# saunamadis.net
KiCad netlist of a schematic drawn in Altium Designer
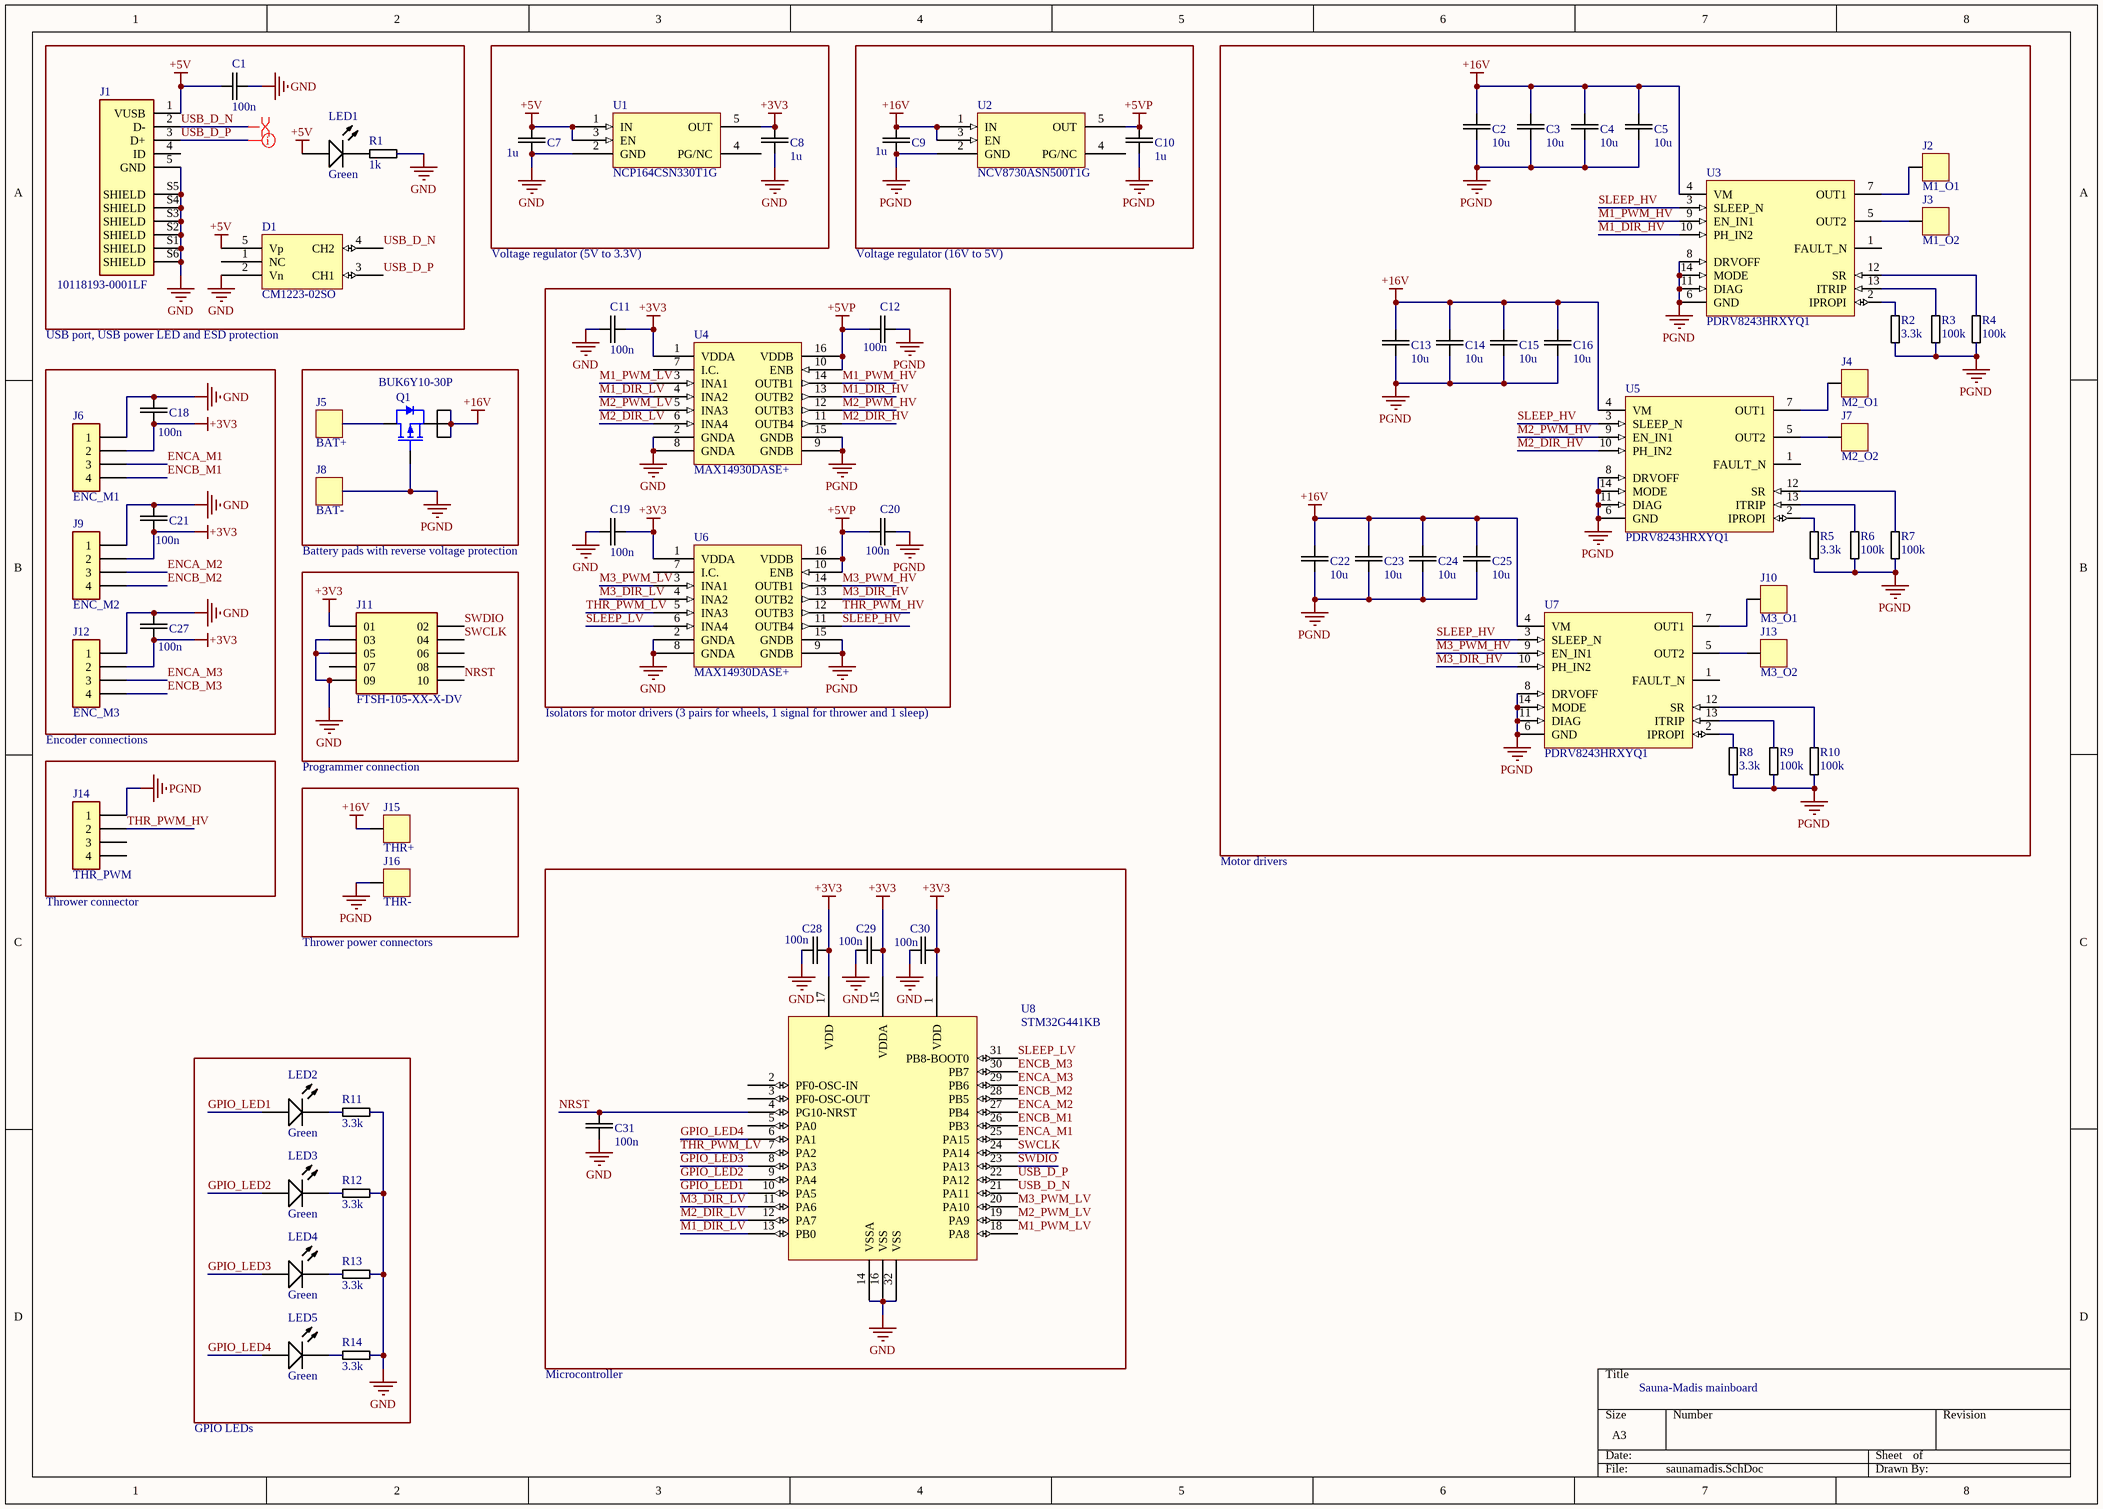
[diagram p0: saunamadis.SchDoc]

(export (version "E")
  (design (tool "Eeschema 10.0.6"))
  (components
    (comp (ref "C1")
      (value "0603C")
      (footprint "0603R")
      (description "Capacitor")
      (fields (field (name "C") "100n"))
      (libsource (lib "comp") (part "0603C"))
    )
    (comp (ref "C2")
      (value "0603C")
      (footprint "1206 cap")
      (description "Capacitor")
      (fields (field (name "C") "10u"))
      (libsource (lib "comp") (part "0603C"))
    )
    (comp (ref "C3")
      (value "0603C")
      (footprint "1206 cap")
      (description "Capacitor")
      (fields (field (name "C") "10u"))
      (libsource (lib "comp") (part "0603C"))
    )
    (comp (ref "C4")
      (value "0603C")
      (footprint "1206 cap")
      (description "Capacitor")
      (fields (field (name "C") "10u"))
      (libsource (lib "comp") (part "0603C"))
    )
    (comp (ref "C5")
      (value "0603C")
      (footprint "1206 cap")
      (description "Capacitor")
      (fields (field (name "C") "10u"))
      (libsource (lib "comp") (part "0603C"))
    )
    (comp (ref "C7")
      (value "0603C")
      (footprint "0603R")
      (description "Capacitor")
      (fields (field (name "C") "1u"))
      (libsource (lib "comp") (part "0603C"))
    )
    (comp (ref "C8")
      (value "0603C")
      (footprint "0603R")
      (description "Capacitor")
      (fields (field (name "C") "1u"))
      (libsource (lib "comp") (part "0603C"))
    )
    (comp (ref "C9")
      (value "0603C")
      (footprint "0603R")
      (description "Capacitor")
      (fields (field (name "C") "1u"))
      (libsource (lib "comp") (part "0603C"))
    )
    (comp (ref "C10")
      (value "0603C")
      (footprint "0603R")
      (description "Capacitor")
      (fields (field (name "C") "1u"))
      (libsource (lib "comp") (part "0603C"))
    )
    (comp (ref "C11")
      (value "0603C")
      (footprint "0603R")
      (description "Capacitor")
      (fields (field (name "C") "100n"))
      (libsource (lib "comp") (part "0603C"))
    )
    (comp (ref "C12")
      (value "0603C")
      (footprint "0603R")
      (description "Capacitor")
      (fields (field (name "C") "100n"))
      (libsource (lib "comp") (part "0603C"))
    )
    (comp (ref "C13")
      (value "0603C")
      (footprint "1206 cap")
      (description "Capacitor")
      (fields (field (name "C") "10u"))
      (libsource (lib "comp") (part "0603C"))
    )
    (comp (ref "C14")
      (value "0603C")
      (footprint "1206 cap")
      (description "Capacitor")
      (fields (field (name "C") "10u"))
      (libsource (lib "comp") (part "0603C"))
    )
    (comp (ref "C15")
      (value "0603C")
      (footprint "1206 cap")
      (description "Capacitor")
      (fields (field (name "C") "10u"))
      (libsource (lib "comp") (part "0603C"))
    )
    (comp (ref "C16")
      (value "0603C")
      (footprint "1206 cap")
      (description "Capacitor")
      (fields (field (name "C") "10u"))
      (libsource (lib "comp") (part "0603C"))
    )
    (comp (ref "C18")
      (value "0603C")
      (footprint "0603R")
      (description "Capacitor")
      (fields (field (name "C") "100n"))
      (libsource (lib "comp") (part "0603C"))
    )
    (comp (ref "C19")
      (value "0603C")
      (footprint "0603R")
      (description "Capacitor")
      (fields (field (name "C") "100n"))
      (libsource (lib "comp") (part "0603C"))
    )
    (comp (ref "C20")
      (value "0603C")
      (footprint "0603R")
      (description "Capacitor")
      (fields (field (name "C") "100n"))
      (libsource (lib "comp") (part "0603C"))
    )
    (comp (ref "C21")
      (value "0603C")
      (footprint "0603R")
      (description "Capacitor")
      (fields (field (name "C") "100n"))
      (libsource (lib "comp") (part "0603C"))
    )
    (comp (ref "C22")
      (value "0603C")
      (footprint "1206 cap")
      (description "Capacitor")
      (fields (field (name "C") "10u"))
      (libsource (lib "comp") (part "0603C"))
    )
    (comp (ref "C23")
      (value "0603C")
      (footprint "1206 cap")
      (description "Capacitor")
      (fields (field (name "C") "10u"))
      (libsource (lib "comp") (part "0603C"))
    )
    (comp (ref "C24")
      (value "0603C")
      (footprint "1206 cap")
      (description "Capacitor")
      (fields (field (name "C") "10u"))
      (libsource (lib "comp") (part "0603C"))
    )
    (comp (ref "C25")
      (value "0603C")
      (footprint "1206 cap")
      (description "Capacitor")
      (fields (field (name "C") "10u"))
      (libsource (lib "comp") (part "0603C"))
    )
    (comp (ref "C27")
      (value "0603C")
      (footprint "0603R")
      (description "Capacitor")
      (fields (field (name "C") "100n"))
      (libsource (lib "comp") (part "0603C"))
    )
    (comp (ref "C28")
      (value "0603C")
      (footprint "0603R")
      (description "Capacitor")
      (fields (field (name "C") "100n"))
      (libsource (lib "comp") (part "0603C"))
    )
    (comp (ref "C29")
      (value "0603C")
      (footprint "0603R")
      (description "Capacitor")
      (fields (field (name "C") "100n"))
      (libsource (lib "comp") (part "0603C"))
    )
    (comp (ref "C30")
      (value "0603C")
      (footprint "0603R")
      (description "Capacitor")
      (fields (field (name "C") "100n"))
      (libsource (lib "comp") (part "0603C"))
    )
    (comp (ref "C31")
      (value "0603C")
      (footprint "0603R")
      (description "Capacitor")
      (fields (field (name "C") "100n"))
      (libsource (lib "comp") (part "0603C"))
    )
    (comp (ref "D1")
      (value "CM1223-02SO")
      (footprint "CM1223-02SO")
      (description "TVS diode")
      (libsource (lib "comp") (part "CM1223-02SO"))
    )
    (comp (ref "J1")
      (value "10118193-0001LF")
      (footprint "FCI_10118193-0001LF")
      (description "USB - micro B USB 2.0 Receptacle Connector 5 Position Surface Mount, Right Angle; Through Hole")
      (fields (field (name "MF") "Amphenol ICC"))
      (libsource (lib "comp") (part "10118193-0001LF"))
    )
    (comp (ref "J2")
      (value "Pad")
      (footprint "Pad")
      (description "PAD")
      (fields (field (name "NAME") "M1_O1"))
      (libsource (lib "comp") (part "Pad"))
    )
    (comp (ref "J3")
      (value "Pad")
      (footprint "Pad")
      (description "PAD")
      (fields (field (name "NAME") "M1_O2"))
      (libsource (lib "comp") (part "Pad"))
    )
    (comp (ref "J4")
      (value "Pad")
      (footprint "Pad")
      (description "PAD")
      (fields (field (name "NAME") "M2_O1"))
      (libsource (lib "comp") (part "Pad"))
    )
    (comp (ref "J5")
      (value "Pad")
      (footprint "Pad")
      (description "PAD")
      (fields (field (name "NAME") "BAT+"))
      (libsource (lib "") (part "Pad_1"))
    )
    (comp (ref "J6")
      (value "ENC_M1")
      (footprint "TE_7-215079-4")
      (description "Micro-MaTch 4 Position 1.27 mm Pitch Vertical Female-on-Board Connector")
      (fields (field (name "MP") "7-215079-4") (field (name "MF") "TE Connectivity"))
      (libsource (lib "comp") (part "7-215079-4"))
    )
    (comp (ref "J7")
      (value "Pad")
      (footprint "Pad")
      (description "PAD")
      (fields (field (name "NAME") "M2_O2"))
      (libsource (lib "comp") (part "Pad"))
    )
    (comp (ref "J8")
      (value "Pad")
      (footprint "Pad")
      (description "PAD")
      (fields (field (name "NAME") "BAT-"))
      (libsource (lib "") (part "Pad_1"))
    )
    (comp (ref "J9")
      (value "ENC_M2")
      (footprint "TE_7-215079-4")
      (description "Micro-MaTch 4 Position 1.27 mm Pitch Vertical Female-on-Board Connector")
      (fields (field (name "MP") "7-215079-4") (field (name "MF") "TE Connectivity"))
      (libsource (lib "comp") (part "7-215079-4"))
    )
    (comp (ref "J10")
      (value "Pad")
      (footprint "Pad")
      (description "PAD")
      (fields (field (name "NAME") "M3_O1"))
      (libsource (lib "comp") (part "Pad"))
    )
    (comp (ref "J11")
      (value "FTSH-105-XX-X-DV")
      (footprint "SAMTEC_FTSH-105-XX-X-DV")
      (description "Connector Header Surface Mount 10 position 0.050\" (1.27mm)")
      (libsource (lib "comp") (part "FTSH-105-XX-X-DV"))
    )
    (comp (ref "J12")
      (value "ENC_M3")
      (footprint "TE_7-215079-4")
      (description "Micro-MaTch 4 Position 1.27 mm Pitch Vertical Female-on-Board Connector")
      (fields (field (name "MP") "7-215079-4") (field (name "MF") "TE Connectivity"))
      (libsource (lib "comp") (part "7-215079-4"))
    )
    (comp (ref "J13")
      (value "Pad")
      (footprint "Pad")
      (description "PAD")
      (fields (field (name "NAME") "M3_O2"))
      (libsource (lib "comp") (part "Pad"))
    )
    (comp (ref "J14")
      (value "THR_PWM")
      (footprint "TE_7-215079-4")
      (description "Micro-MaTch 4 Position 1.27 mm Pitch Vertical Female-on-Board Connector")
      (fields (field (name "MP") "7-215079-4") (field (name "MF") "TE Connectivity"))
      (libsource (lib "comp") (part "7-215079-4"))
    )
    (comp (ref "J15")
      (value "Pad")
      (footprint "Pad")
      (description "PAD")
      (fields (field (name "NAME") "THR+"))
      (libsource (lib "comp") (part "Pad"))
    )
    (comp (ref "J16")
      (value "Pad")
      (footprint "Pad")
      (description "PAD")
      (fields (field (name "NAME") "THR-"))
      (libsource (lib "comp") (part "Pad"))
    )
    (comp (ref "LED1")
      (value "LED")
      (footprint "LEDwhite0603")
      (description "led")
      (fields (field (name "COLOR") "Green"))
      (libsource (lib "comp") (part "LED"))
    )
    (comp (ref "LED2")
      (value "LED")
      (footprint "LEDwhite0603")
      (description "led")
      (fields (field (name "COLOR") "Green"))
      (libsource (lib "comp") (part "LED"))
    )
    (comp (ref "LED3")
      (value "LED")
      (footprint "LEDwhite0603")
      (description "led")
      (fields (field (name "COLOR") "Green"))
      (libsource (lib "comp") (part "LED"))
    )
    (comp (ref "LED4")
      (value "LED")
      (footprint "LEDwhite0603")
      (description "led")
      (fields (field (name "COLOR") "Green"))
      (libsource (lib "comp") (part "LED"))
    )
    (comp (ref "LED5")
      (value "LED")
      (footprint "LEDwhite0603")
      (description "led")
      (fields (field (name "COLOR") "Green"))
      (libsource (lib "comp") (part "LED"))
    )
    (comp (ref "Q1")
      (value "BUK6Y10-30P")
      (footprint "BUK6Y10-30P")
      (description "Reverse voltage protection")
      (libsource (lib "comp") (part "BUK6Y10-30P"))
    )
    (comp (ref "R1")
      (value "0603R")
      (footprint "0603R")
      (description "resistor")
      (fields (field (name "RESISTANCE") "1k"))
      (libsource (lib "comp") (part "0603R"))
    )
    (comp (ref "R2")
      (value "0603R")
      (footprint "0603R")
      (description "resistor")
      (fields (field (name "RESISTANCE") "3.3k"))
      (libsource (lib "comp") (part "0603R"))
    )
    (comp (ref "R3")
      (value "0603R")
      (footprint "0603R")
      (description "resistor")
      (fields (field (name "RESISTANCE") "100k"))
      (libsource (lib "comp") (part "0603R"))
    )
    (comp (ref "R4")
      (value "0603R")
      (footprint "0603R")
      (description "resistor")
      (fields (field (name "RESISTANCE") "100k"))
      (libsource (lib "comp") (part "0603R"))
    )
    (comp (ref "R5")
      (value "0603R")
      (footprint "0603R")
      (description "resistor")
      (fields (field (name "RESISTANCE") "3.3k"))
      (libsource (lib "comp") (part "0603R"))
    )
    (comp (ref "R6")
      (value "0603R")
      (footprint "0603R")
      (description "resistor")
      (fields (field (name "RESISTANCE") "100k"))
      (libsource (lib "comp") (part "0603R"))
    )
    (comp (ref "R7")
      (value "0603R")
      (footprint "0603R")
      (description "resistor")
      (fields (field (name "RESISTANCE") "100k"))
      (libsource (lib "comp") (part "0603R"))
    )
    (comp (ref "R8")
      (value "0603R")
      (footprint "0603R")
      (description "resistor")
      (fields (field (name "RESISTANCE") "3.3k"))
      (libsource (lib "comp") (part "0603R"))
    )
    (comp (ref "R9")
      (value "0603R")
      (footprint "0603R")
      (description "resistor")
      (fields (field (name "RESISTANCE") "100k"))
      (libsource (lib "comp") (part "0603R"))
    )
    (comp (ref "R10")
      (value "0603R")
      (footprint "0603R")
      (description "resistor")
      (fields (field (name "RESISTANCE") "100k"))
      (libsource (lib "comp") (part "0603R"))
    )
    (comp (ref "R11")
      (value "0603R")
      (footprint "0603R")
      (description "resistor")
      (fields (field (name "RESISTANCE") "3.3k"))
      (libsource (lib "comp") (part "0603R"))
    )
    (comp (ref "R12")
      (value "0603R")
      (footprint "0603R")
      (description "resistor")
      (fields (field (name "RESISTANCE") "3.3k"))
      (libsource (lib "comp") (part "0603R"))
    )
    (comp (ref "R13")
      (value "0603R")
      (footprint "0603R")
      (description "resistor")
      (fields (field (name "RESISTANCE") "3.3k"))
      (libsource (lib "comp") (part "0603R"))
    )
    (comp (ref "R14")
      (value "0603R")
      (footprint "0603R")
      (description "resistor")
      (fields (field (name "RESISTANCE") "3.3k"))
      (libsource (lib "comp") (part "0603R"))
    )
    (comp (ref "U1")
      (value "NCP164CSN330T1G")
      (footprint "NCP164CSN330T1G/NCV8730ASN500T1G")
      (description "Voltage regulator for microcontroller")
      (libsource (lib "comp") (part "NCP164CSN330T1G"))
    )
    (comp (ref "U2")
      (value "NCV8730ASN500T1G")
      (footprint "NCP164CSN330T1G/NCV8730ASN500T1G")
      (description "Voltage regulator at the motor driver’s side")
      (libsource (lib "comp") (part "NCV8730ASN500T1G"))
    )
    (comp (ref "U3")
      (value "PDRV8243HRXYQ1")
      (footprint "PDRV8243HRXYQ1")
      (description "Motor driver")
      (libsource (lib "comp") (part "PDRV8243HRXYQ1"))
    )
    (comp (ref "U4")
      (value "MAX14930DASE+")
      (footprint "MAX14930DASE+")
      (description "isolator")
      (libsource (lib "comp") (part "MAX14930DASE+"))
    )
    (comp (ref "U5")
      (value "PDRV8243HRXYQ1")
      (footprint "PDRV8243HRXYQ1")
      (description "Motor driver")
      (libsource (lib "comp") (part "PDRV8243HRXYQ1"))
    )
    (comp (ref "U6")
      (value "MAX14930DASE+")
      (footprint "MAX14930DASE+")
      (description "isolator")
      (libsource (lib "comp") (part "MAX14930DASE+"))
    )
    (comp (ref "U7")
      (value "PDRV8243HRXYQ1")
      (footprint "PDRV8243HRXYQ1")
      (description "Motor driver")
      (libsource (lib "comp") (part "PDRV8243HRXYQ1"))
    )
    (comp (ref "U8")
      (value "STM32G441KB")
      (footprint "TQFP80P900X900X160-32N")
      (description "microcontroller")
      (libsource (lib "comp") (part "STM32G441KB"))
    )
  )
  (nets
    (net (code "1") (name "+3V3") (class "Default")
      (node (ref "C11") (pin "1") (pinfunction "1_1") (pintype "passive"))
      (node (ref "C18") (pin "1") (pinfunction "1_1") (pintype "passive"))
      (node (ref "C19") (pin "1") (pinfunction "1_1") (pintype "passive"))
      (node (ref "C21") (pin "1") (pinfunction "1_1") (pintype "passive"))
      (node (ref "C27") (pin "1") (pinfunction "1_1") (pintype "passive"))
      (node (ref "C28") (pin "1") (pinfunction "1_1") (pintype "passive"))
      (node (ref "C29") (pin "1") (pinfunction "1_1") (pintype "passive"))
      (node (ref "C30") (pin "1") (pinfunction "1_1") (pintype "passive"))
      (node (ref "C8") (pin "2") (pinfunction "2_2") (pintype "passive"))
      (node (ref "J11") (pin "01") (pinfunction "01_01") (pintype "passive"))
      (node (ref "J12") (pin "2") (pinfunction "2_2") (pintype "passive"))
      (node (ref "J6") (pin "2") (pinfunction "2_2") (pintype "passive"))
      (node (ref "J9") (pin "2") (pinfunction "2_2") (pintype "passive"))
      (node (ref "U1") (pin "5") (pinfunction "OUT_5") (pintype "power_in"))
      (node (ref "U4") (pin "1") (pinfunction "VDDA_1") (pintype "power_in"))
      (node (ref "U6") (pin "1") (pinfunction "VDDA_1") (pintype "power_in"))
      (node (ref "U8") (pin "1") (pinfunction "VDD_1") (pintype "power_in"))
      (node (ref "U8") (pin "15") (pinfunction "VDDA_15") (pintype "power_in"))
      (node (ref "U8") (pin "17") (pinfunction "VDD_17") (pintype "power_in"))
    )
    (net (code "2") (name "+5V") (class "Default")
      (node (ref "C1") (pin "1") (pinfunction "1_1") (pintype "passive"))
      (node (ref "C7") (pin "2") (pinfunction "2_2") (pintype "passive"))
      (node (ref "D1") (pin "5") (pinfunction "Vp_5") (pintype "power_in"))
      (node (ref "J1") (pin "1") (pinfunction "VUSB_1") (pintype "passive"))
      (node (ref "LED1") (pin "1") (pinfunction "A_1") (pintype "passive"))
      (node (ref "U1") (pin "1") (pinfunction "IN_1") (pintype "input"))
      (node (ref "U1") (pin "3") (pinfunction "EN_3") (pintype "input"))
    )
    (net (code "3") (name "+5VP") (class "Default")
      (node (ref "C10") (pin "2") (pinfunction "2_2") (pintype "passive"))
      (node (ref "C12") (pin "2") (pinfunction "2_2") (pintype "passive"))
      (node (ref "C20") (pin "2") (pinfunction "2_2") (pintype "passive"))
      (node (ref "U2") (pin "5") (pinfunction "OUT_5") (pintype "power_in"))
      (node (ref "U4") (pin "10") (pinfunction "ENB_10") (pintype "input"))
      (node (ref "U4") (pin "16") (pinfunction "VDDB_16") (pintype "power_in"))
      (node (ref "U6") (pin "10") (pinfunction "ENB_10") (pintype "input"))
      (node (ref "U6") (pin "16") (pinfunction "VDDB_16") (pintype "power_in"))
    )
    (net (code "4") (name "+16V") (class "Default")
      (node (ref "C13") (pin "1") (pinfunction "1_1") (pintype "passive"))
      (node (ref "C14") (pin "1") (pinfunction "1_1") (pintype "passive"))
      (node (ref "C15") (pin "1") (pinfunction "1_1") (pintype "passive"))
      (node (ref "C16") (pin "1") (pinfunction "1_1") (pintype "passive"))
      (node (ref "C2") (pin "1") (pinfunction "1_1") (pintype "passive"))
      (node (ref "C22") (pin "1") (pinfunction "1_1") (pintype "passive"))
      (node (ref "C23") (pin "1") (pinfunction "1_1") (pintype "passive"))
      (node (ref "C24") (pin "1") (pinfunction "1_1") (pintype "passive"))
      (node (ref "C25") (pin "1") (pinfunction "1_1") (pintype "passive"))
      (node (ref "C3") (pin "1") (pinfunction "1_1") (pintype "passive"))
      (node (ref "C4") (pin "1") (pinfunction "1_1") (pintype "passive"))
      (node (ref "C5") (pin "1") (pinfunction "1_1") (pintype "passive"))
      (node (ref "C9") (pin "2") (pinfunction "2_2") (pintype "passive"))
      (node (ref "J15") (pin "1") (pinfunction "1_1") (pintype "passive"))
      (node (ref "Q1") (pin "1") (pinfunction "SOURCE_1") (pintype "passive"))
      (node (ref "Q1") (pin "2") (pinfunction "SOURCE_2") (pintype "passive"))
      (node (ref "Q1") (pin "3") (pinfunction "SOURCE_3") (pintype "passive"))
      (node (ref "U2") (pin "1") (pinfunction "IN_1") (pintype "input"))
      (node (ref "U2") (pin "3") (pinfunction "EN_3") (pintype "input"))
      (node (ref "U3") (pin "4") (pinfunction "VM_4") (pintype "power_in"))
      (node (ref "U5") (pin "4") (pinfunction "VM_4") (pintype "power_in"))
      (node (ref "U7") (pin "4") (pinfunction "VM_4") (pintype "power_in"))
    )
    (net (code "5") (name "/ENCA_M1") (class "Default")
      (node (ref "J6") (pin "3") (pinfunction "3_3") (pintype "passive"))
      (node (ref "U8") (pin "25") (pinfunction "PA15_25") (pintype "bidirectional"))
    )
    (net (code "6") (name "/ENCA_M2") (class "Default")
      (node (ref "J9") (pin "3") (pinfunction "3_3") (pintype "passive"))
      (node (ref "U8") (pin "27") (pinfunction "PB4_27") (pintype "bidirectional"))
    )
    (net (code "7") (name "/ENCA_M3") (class "Default")
      (node (ref "J12") (pin "3") (pinfunction "3_3") (pintype "passive"))
      (node (ref "U8") (pin "29") (pinfunction "PB6_29") (pintype "bidirectional"))
    )
    (net (code "8") (name "/ENCB_M1") (class "Default")
      (node (ref "J6") (pin "4") (pinfunction "4_4") (pintype "passive"))
      (node (ref "U8") (pin "26") (pinfunction "PB3_26") (pintype "bidirectional"))
    )
    (net (code "9") (name "/ENCB_M2") (class "Default")
      (node (ref "J9") (pin "4") (pinfunction "4_4") (pintype "passive"))
      (node (ref "U8") (pin "28") (pinfunction "PB5_28") (pintype "bidirectional"))
    )
    (net (code "10") (name "/ENCB_M3") (class "Default")
      (node (ref "J12") (pin "4") (pinfunction "4_4") (pintype "passive"))
      (node (ref "U8") (pin "30") (pinfunction "PB7_30") (pintype "bidirectional"))
    )
    (net (code "11") (name "/GPIO_LED1") (class "Default")
      (node (ref "LED2") (pin "1") (pinfunction "A_1") (pintype "passive"))
      (node (ref "U8") (pin "10") (pinfunction "PA5_10") (pintype "bidirectional"))
    )
    (net (code "12") (name "/GPIO_LED2") (class "Default")
      (node (ref "LED3") (pin "1") (pinfunction "A_1") (pintype "passive"))
      (node (ref "U8") (pin "9") (pinfunction "PA4_9") (pintype "bidirectional"))
    )
    (net (code "13") (name "/GPIO_LED3") (class "Default")
      (node (ref "LED4") (pin "1") (pinfunction "A_1") (pintype "passive"))
      (node (ref "U8") (pin "8") (pinfunction "PA3_8") (pintype "bidirectional"))
    )
    (net (code "14") (name "/GPIO_LED4") (class "Default")
      (node (ref "LED5") (pin "1") (pinfunction "A_1") (pintype "passive"))
      (node (ref "U8") (pin "6") (pinfunction "PA1_6") (pintype "bidirectional"))
    )
    (net (code "15") (name "/M1_DIR_HV") (class "Default")
      (node (ref "U3") (pin "10") (pinfunction "PH_IN2_10") (pintype "input"))
      (node (ref "U4") (pin "13") (pinfunction "OUTB2_13") (pintype "output"))
    )
    (net (code "16") (name "/M1_DIR_LV") (class "Default")
      (node (ref "U4") (pin "4") (pinfunction "INA2_4") (pintype "input"))
      (node (ref "U8") (pin "13") (pinfunction "PB0_13") (pintype "bidirectional"))
    )
    (net (code "17") (name "/M1_PWM_HV") (class "Default")
      (node (ref "U3") (pin "9") (pinfunction "EN_IN1_9") (pintype "input"))
      (node (ref "U4") (pin "14") (pinfunction "OUTB1_14") (pintype "output"))
    )
    (net (code "18") (name "/M1_PWM_LV") (class "Default")
      (node (ref "U4") (pin "3") (pinfunction "INA1_3") (pintype "input"))
      (node (ref "U8") (pin "18") (pinfunction "PA8_18") (pintype "bidirectional"))
    )
    (net (code "19") (name "/M2_DIR_HV") (class "Default")
      (node (ref "U4") (pin "11") (pinfunction "OUTB4_11") (pintype "output"))
      (node (ref "U5") (pin "10") (pinfunction "PH_IN2_10") (pintype "input"))
    )
    (net (code "20") (name "/M2_DIR_LV") (class "Default")
      (node (ref "U4") (pin "6") (pinfunction "INA4_6") (pintype "input"))
      (node (ref "U8") (pin "12") (pinfunction "PA7_12") (pintype "bidirectional"))
    )
    (net (code "21") (name "/M2_PWM_HV") (class "Default")
      (node (ref "U4") (pin "12") (pinfunction "OUTB3_12") (pintype "output"))
      (node (ref "U5") (pin "9") (pinfunction "EN_IN1_9") (pintype "input"))
    )
    (net (code "22") (name "/M2_PWM_LV") (class "Default")
      (node (ref "U4") (pin "5") (pinfunction "INA3_5") (pintype "input"))
      (node (ref "U8") (pin "19") (pinfunction "PA9_19") (pintype "bidirectional"))
    )
    (net (code "23") (name "/M3_DIR_HV") (class "Default")
      (node (ref "U6") (pin "13") (pinfunction "OUTB2_13") (pintype "output"))
      (node (ref "U7") (pin "10") (pinfunction "PH_IN2_10") (pintype "input"))
    )
    (net (code "24") (name "/M3_DIR_LV") (class "Default")
      (node (ref "U6") (pin "4") (pinfunction "INA2_4") (pintype "input"))
      (node (ref "U8") (pin "11") (pinfunction "PA6_11") (pintype "bidirectional"))
    )
    (net (code "25") (name "/M3_PWM_HV") (class "Default")
      (node (ref "U6") (pin "14") (pinfunction "OUTB1_14") (pintype "output"))
      (node (ref "U7") (pin "9") (pinfunction "EN_IN1_9") (pintype "input"))
    )
    (net (code "26") (name "/M3_PWM_LV") (class "Default")
      (node (ref "U6") (pin "3") (pinfunction "INA1_3") (pintype "input"))
      (node (ref "U8") (pin "20") (pinfunction "PA10_20") (pintype "bidirectional"))
    )
    (net (code "27") (name "/NRST") (class "Default")
      (node (ref "C31") (pin "1") (pinfunction "1_1") (pintype "passive"))
      (node (ref "J11") (pin "10") (pinfunction "10_10") (pintype "passive"))
      (node (ref "U8") (pin "4") (pinfunction "PG10-NRST_4") (pintype "bidirectional"))
    )
    (net (code "28") (name "/SLEEP_HV") (class "Default")
      (node (ref "U3") (pin "3") (pinfunction "SLEEP_N_3") (pintype "input"))
      (node (ref "U5") (pin "3") (pinfunction "SLEEP_N_3") (pintype "input"))
      (node (ref "U6") (pin "11") (pinfunction "OUTB4_11") (pintype "output"))
      (node (ref "U7") (pin "3") (pinfunction "SLEEP_N_3") (pintype "input"))
    )
    (net (code "29") (name "/SLEEP_LV") (class "Default")
      (node (ref "U6") (pin "6") (pinfunction "INA4_6") (pintype "input"))
      (node (ref "U8") (pin "31") (pinfunction "PB8-BOOT0_31") (pintype "bidirectional"))
    )
    (net (code "30") (name "/SWCLK") (class "Default")
      (node (ref "J11") (pin "04") (pinfunction "04_04") (pintype "passive"))
      (node (ref "U8") (pin "24") (pinfunction "PA14_24") (pintype "bidirectional"))
    )
    (net (code "31") (name "/SWDIO") (class "Default")
      (node (ref "J11") (pin "02") (pinfunction "02_02") (pintype "passive"))
      (node (ref "U8") (pin "23") (pinfunction "PA13_23") (pintype "bidirectional"))
    )
    (net (code "32") (name "/THR_PWM_HV") (class "Default")
      (node (ref "J14") (pin "2") (pinfunction "2_2") (pintype "passive"))
      (node (ref "U6") (pin "12") (pinfunction "OUTB3_12") (pintype "output"))
    )
    (net (code "33") (name "/THR_PWM_LV") (class "Default")
      (node (ref "U6") (pin "5") (pinfunction "INA3_5") (pintype "input"))
      (node (ref "U8") (pin "7") (pinfunction "PA2_7") (pintype "bidirectional"))
    )
    (net (code "34") (name "/USB_D_N") (class "Default")
      (node (ref "D1") (pin "4") (pinfunction "CH2_4") (pintype "bidirectional"))
      (node (ref "J1") (pin "2") (pinfunction "D-_2") (pintype "passive"))
      (node (ref "U8") (pin "21") (pinfunction "PA11_21") (pintype "bidirectional"))
    )
    (net (code "35") (name "/USB_D_P") (class "Default")
      (node (ref "D1") (pin "3") (pinfunction "CH1_3") (pintype "bidirectional"))
      (node (ref "J1") (pin "3") (pinfunction "D+_3") (pintype "passive"))
      (node (ref "U8") (pin "22") (pinfunction "PA12_22") (pintype "bidirectional"))
    )
    (net (code "36") (name "GND") (class "Default")
      (node (ref "C1") (pin "2") (pinfunction "2_2") (pintype "passive"))
      (node (ref "C11") (pin "2") (pinfunction "2_2") (pintype "passive"))
      (node (ref "C18") (pin "2") (pinfunction "2_2") (pintype "passive"))
      (node (ref "C19") (pin "2") (pinfunction "2_2") (pintype "passive"))
      (node (ref "C21") (pin "2") (pinfunction "2_2") (pintype "passive"))
      (node (ref "C27") (pin "2") (pinfunction "2_2") (pintype "passive"))
      (node (ref "C28") (pin "2") (pinfunction "2_2") (pintype "passive"))
      (node (ref "C29") (pin "2") (pinfunction "2_2") (pintype "passive"))
      (node (ref "C30") (pin "2") (pinfunction "2_2") (pintype "passive"))
      (node (ref "C31") (pin "2") (pinfunction "2_2") (pintype "passive"))
      (node (ref "C7") (pin "1") (pinfunction "1_1") (pintype "passive"))
      (node (ref "C8") (pin "1") (pinfunction "1_1") (pintype "passive"))
      (node (ref "D1") (pin "2") (pinfunction "Vn_2") (pintype "power_in"))
      (node (ref "J1") (pin "5") (pinfunction "GND_5") (pintype "passive"))
      (node (ref "J1") (pin "S1") (pinfunction "SHIELD_S1") (pintype "passive"))
      (node (ref "J1") (pin "S2") (pinfunction "SHIELD_S2") (pintype "passive"))
      (node (ref "J1") (pin "S3") (pinfunction "SHIELD_S3") (pintype "passive"))
      (node (ref "J1") (pin "S4") (pinfunction "SHIELD_S4") (pintype "passive"))
      (node (ref "J1") (pin "S5") (pinfunction "SHIELD_S5") (pintype "passive"))
      (node (ref "J1") (pin "S6") (pinfunction "SHIELD_S6") (pintype "passive"))
      (node (ref "J11") (pin "03") (pinfunction "03_03") (pintype "passive"))
      (node (ref "J11") (pin "05") (pinfunction "05_05") (pintype "passive"))
      (node (ref "J11") (pin "09") (pinfunction "09_09") (pintype "passive"))
      (node (ref "J12") (pin "1") (pinfunction "1_1") (pintype "passive"))
      (node (ref "J6") (pin "1") (pinfunction "1_1") (pintype "passive"))
      (node (ref "J9") (pin "1") (pinfunction "1_1") (pintype "passive"))
      (node (ref "R1") (pin "2") (pinfunction "2_2") (pintype "passive"))
      (node (ref "R11") (pin "1") (pinfunction "1_1") (pintype "passive"))
      (node (ref "R12") (pin "1") (pinfunction "1_1") (pintype "passive"))
      (node (ref "R13") (pin "1") (pinfunction "1_1") (pintype "passive"))
      (node (ref "R14") (pin "1") (pinfunction "1_1") (pintype "passive"))
      (node (ref "U1") (pin "2") (pinfunction "GND_2") (pintype "power_in"))
      (node (ref "U4") (pin "2") (pinfunction "GNDA_2") (pintype "power_in"))
      (node (ref "U4") (pin "8") (pinfunction "GNDA_8") (pintype "power_in"))
      (node (ref "U6") (pin "2") (pinfunction "GNDA_2") (pintype "power_in"))
      (node (ref "U6") (pin "8") (pinfunction "GNDA_8") (pintype "power_in"))
    )
    (net (code "37") (name "Net-(LED1-K)") (class "Default")
      (node (ref "LED1") (pin "2") (pinfunction "K_2") (pintype "passive"))
      (node (ref "R1") (pin "1") (pinfunction "1_1") (pintype "passive"))
    )
    (net (code "38") (name "Net-(LED2-K)") (class "Default")
      (node (ref "LED2") (pin "2") (pinfunction "K_2") (pintype "passive"))
      (node (ref "R11") (pin "2") (pinfunction "2_2") (pintype "passive"))
    )
    (net (code "39") (name "Net-(LED3-K)") (class "Default")
      (node (ref "LED3") (pin "2") (pinfunction "K_2") (pintype "passive"))
      (node (ref "R12") (pin "2") (pinfunction "2_2") (pintype "passive"))
    )
    (net (code "40") (name "Net-(LED4-K)") (class "Default")
      (node (ref "LED4") (pin "2") (pinfunction "K_2") (pintype "passive"))
      (node (ref "R13") (pin "2") (pinfunction "2_2") (pintype "passive"))
    )
    (net (code "41") (name "Net-(LED5-K)") (class "Default")
      (node (ref "LED5") (pin "2") (pinfunction "K_2") (pintype "passive"))
      (node (ref "R14") (pin "2") (pinfunction "2_2") (pintype "passive"))
    )
    (net (code "42") (name "Net-(Q1-DRAIN)") (class "Default")
      (node (ref "J5") (pin "1") (pinfunction "1_1") (pintype "passive"))
      (node (ref "Q1") (pin "5") (pinfunction "DRAIN_5") (pintype "passive"))
    )
    (net (code "43") (name "Net-(U3-IPROPI)") (class "Default")
      (node (ref "R2") (pin "2") (pinfunction "2_2") (pintype "passive"))
      (node (ref "U3") (pin "2") (pinfunction "IPROPI_2") (pintype "bidirectional"))
    )
    (net (code "44") (name "Net-(U3-ITRIP)") (class "Default")
      (node (ref "R3") (pin "1") (pinfunction "1_1") (pintype "passive"))
      (node (ref "U3") (pin "13") (pinfunction "ITRIP_13") (pintype "input"))
    )
    (net (code "45") (name "Net-(U3-OUT1)") (class "Default")
      (node (ref "J2") (pin "1") (pinfunction "1_1") (pintype "passive"))
      (node (ref "U3") (pin "7") (pinfunction "OUT1_7") (pintype "passive"))
    )
    (net (code "46") (name "Net-(U3-OUT2)") (class "Default")
      (node (ref "J3") (pin "1") (pinfunction "1_1") (pintype "passive"))
      (node (ref "U3") (pin "5") (pinfunction "OUT2_5") (pintype "passive"))
    )
    (net (code "47") (name "Net-(U3-SR)") (class "Default")
      (node (ref "R4") (pin "1") (pinfunction "1_1") (pintype "passive"))
      (node (ref "U3") (pin "12") (pinfunction "SR_12") (pintype "input"))
    )
    (net (code "48") (name "Net-(U5-IPROPI)") (class "Default")
      (node (ref "R5") (pin "2") (pinfunction "2_2") (pintype "passive"))
      (node (ref "U5") (pin "2") (pinfunction "IPROPI_2") (pintype "bidirectional"))
    )
    (net (code "49") (name "Net-(U5-ITRIP)") (class "Default")
      (node (ref "R6") (pin "1") (pinfunction "1_1") (pintype "passive"))
      (node (ref "U5") (pin "13") (pinfunction "ITRIP_13") (pintype "input"))
    )
    (net (code "50") (name "Net-(U5-OUT1)") (class "Default")
      (node (ref "J4") (pin "1") (pinfunction "1_1") (pintype "passive"))
      (node (ref "U5") (pin "7") (pinfunction "OUT1_7") (pintype "passive"))
    )
    (net (code "51") (name "Net-(U5-OUT2)") (class "Default")
      (node (ref "J7") (pin "1") (pinfunction "1_1") (pintype "passive"))
      (node (ref "U5") (pin "5") (pinfunction "OUT2_5") (pintype "passive"))
    )
    (net (code "52") (name "Net-(U5-SR)") (class "Default")
      (node (ref "R7") (pin "1") (pinfunction "1_1") (pintype "passive"))
      (node (ref "U5") (pin "12") (pinfunction "SR_12") (pintype "input"))
    )
    (net (code "53") (name "Net-(U7-IPROPI)") (class "Default")
      (node (ref "R8") (pin "2") (pinfunction "2_2") (pintype "passive"))
      (node (ref "U7") (pin "2") (pinfunction "IPROPI_2") (pintype "bidirectional"))
    )
    (net (code "54") (name "Net-(U7-ITRIP)") (class "Default")
      (node (ref "R9") (pin "1") (pinfunction "1_1") (pintype "passive"))
      (node (ref "U7") (pin "13") (pinfunction "ITRIP_13") (pintype "input"))
    )
    (net (code "55") (name "Net-(U7-OUT1)") (class "Default")
      (node (ref "J10") (pin "1") (pinfunction "1_1") (pintype "passive"))
      (node (ref "U7") (pin "7") (pinfunction "OUT1_7") (pintype "passive"))
    )
    (net (code "56") (name "Net-(U7-OUT2)") (class "Default")
      (node (ref "J13") (pin "1") (pinfunction "1_1") (pintype "passive"))
      (node (ref "U7") (pin "5") (pinfunction "OUT2_5") (pintype "passive"))
    )
    (net (code "57") (name "Net-(U7-SR)") (class "Default")
      (node (ref "R10") (pin "1") (pinfunction "1_1") (pintype "passive"))
      (node (ref "U7") (pin "12") (pinfunction "SR_12") (pintype "input"))
    )
    (net (code "58") (name "PGND") (class "Default")
      (node (ref "C10") (pin "1") (pinfunction "1_1") (pintype "passive"))
      (node (ref "C12") (pin "1") (pinfunction "1_1") (pintype "passive"))
      (node (ref "C13") (pin "2") (pinfunction "2_2") (pintype "passive"))
      (node (ref "C14") (pin "2") (pinfunction "2_2") (pintype "passive"))
      (node (ref "C15") (pin "2") (pinfunction "2_2") (pintype "passive"))
      (node (ref "C16") (pin "2") (pinfunction "2_2") (pintype "passive"))
      (node (ref "C2") (pin "2") (pinfunction "2_2") (pintype "passive"))
      (node (ref "C20") (pin "1") (pinfunction "1_1") (pintype "passive"))
      (node (ref "C22") (pin "2") (pinfunction "2_2") (pintype "passive"))
      (node (ref "C23") (pin "2") (pinfunction "2_2") (pintype "passive"))
      (node (ref "C24") (pin "2") (pinfunction "2_2") (pintype "passive"))
      (node (ref "C25") (pin "2") (pinfunction "2_2") (pintype "passive"))
      (node (ref "C3") (pin "2") (pinfunction "2_2") (pintype "passive"))
      (node (ref "C4") (pin "2") (pinfunction "2_2") (pintype "passive"))
      (node (ref "C5") (pin "2") (pinfunction "2_2") (pintype "passive"))
      (node (ref "C9") (pin "1") (pinfunction "1_1") (pintype "passive"))
      (node (ref "J14") (pin "1") (pinfunction "1_1") (pintype "passive"))
      (node (ref "J16") (pin "1") (pinfunction "1_1") (pintype "passive"))
      (node (ref "J8") (pin "1") (pinfunction "1_1") (pintype "passive"))
      (node (ref "Q1") (pin "4") (pinfunction "GATE_4") (pintype "passive"))
      (node (ref "R10") (pin "2") (pinfunction "2_2") (pintype "passive"))
      (node (ref "R2") (pin "1") (pinfunction "1_1") (pintype "passive"))
      (node (ref "R3") (pin "2") (pinfunction "2_2") (pintype "passive"))
      (node (ref "R4") (pin "2") (pinfunction "2_2") (pintype "passive"))
      (node (ref "R5") (pin "1") (pinfunction "1_1") (pintype "passive"))
      (node (ref "R6") (pin "2") (pinfunction "2_2") (pintype "passive"))
      (node (ref "R7") (pin "2") (pinfunction "2_2") (pintype "passive"))
      (node (ref "R8") (pin "1") (pinfunction "1_1") (pintype "passive"))
      (node (ref "R9") (pin "2") (pinfunction "2_2") (pintype "passive"))
      (node (ref "U2") (pin "2") (pinfunction "GND_2") (pintype "power_in"))
      (node (ref "U3") (pin "11") (pinfunction "DIAG_11") (pintype "input"))
      (node (ref "U3") (pin "14") (pinfunction "MODE_14") (pintype "input"))
      (node (ref "U3") (pin "6") (pinfunction "GND_6") (pintype "power_in"))
      (node (ref "U3") (pin "8") (pinfunction "DRVOFF_8") (pintype "input"))
      (node (ref "U4") (pin "15") (pinfunction "GNDB_15") (pintype "power_in"))
      (node (ref "U4") (pin "9") (pinfunction "GNDB_9") (pintype "power_in"))
      (node (ref "U5") (pin "11") (pinfunction "DIAG_11") (pintype "input"))
      (node (ref "U5") (pin "14") (pinfunction "MODE_14") (pintype "input"))
      (node (ref "U5") (pin "6") (pinfunction "GND_6") (pintype "power_in"))
      (node (ref "U5") (pin "8") (pinfunction "DRVOFF_8") (pintype "input"))
      (node (ref "U6") (pin "15") (pinfunction "GNDB_15") (pintype "power_in"))
      (node (ref "U6") (pin "9") (pinfunction "GNDB_9") (pintype "power_in"))
      (node (ref "U7") (pin "11") (pinfunction "DIAG_11") (pintype "input"))
      (node (ref "U7") (pin "14") (pinfunction "MODE_14") (pintype "input"))
      (node (ref "U7") (pin "6") (pinfunction "GND_6") (pintype "power_in"))
      (node (ref "U7") (pin "8") (pinfunction "DRVOFF_8") (pintype "input"))
    )
    (net (code "59") (name "unconnected-(D1-NC-Pad1)") (class "Default")
      (node (ref "D1") (pin "1") (pinfunction "NC_1") (pintype "power_in"))
    )
    (net (code "60") (name "unconnected-(J1-ID-Pad4)") (class "Default")
      (node (ref "J1") (pin "4") (pinfunction "ID_4") (pintype "passive"))
    )
    (net (code "61") (name "unconnected-(J11-Pad06)") (class "Default")
      (node (ref "J11") (pin "06") (pinfunction "06_06") (pintype "passive"))
    )
    (net (code "62") (name "unconnected-(J11-Pad07)") (class "Default")
      (node (ref "J11") (pin "07") (pinfunction "07_07") (pintype "passive"))
    )
    (net (code "63") (name "unconnected-(J11-Pad08)") (class "Default")
      (node (ref "J11") (pin "08") (pinfunction "08_08") (pintype "passive"))
    )
    (net (code "64") (name "unconnected-(J14-Pad3)") (class "Default")
      (node (ref "J14") (pin "3") (pinfunction "3_3") (pintype "passive"))
    )
    (net (code "65") (name "unconnected-(J14-Pad4)") (class "Default")
      (node (ref "J14") (pin "4") (pinfunction "4_4") (pintype "passive"))
    )
    (net (code "66") (name "unconnected-(U1-PG{slash}NC-Pad4)") (class "Default")
      (node (ref "U1") (pin "4") (pinfunction "PG/NC_4") (pintype "open_collector"))
    )
    (net (code "67") (name "unconnected-(U2-PG{slash}NC-Pad4)") (class "Default")
      (node (ref "U2") (pin "4") (pinfunction "PG/NC_4") (pintype "open_collector"))
    )
    (net (code "68") (name "unconnected-(U3-FAULT_N-Pad1)") (class "Default")
      (node (ref "U3") (pin "1") (pinfunction "FAULT_N_1") (pintype "open_collector"))
    )
    (net (code "69") (name "unconnected-(U4-I.C.-Pad7)") (class "Default")
      (node (ref "U4") (pin "7") (pinfunction "I.C._7") (pintype "power_in"))
    )
    (net (code "70") (name "unconnected-(U5-FAULT_N-Pad1)") (class "Default")
      (node (ref "U5") (pin "1") (pinfunction "FAULT_N_1") (pintype "open_collector"))
    )
    (net (code "71") (name "unconnected-(U6-I.C.-Pad7)") (class "Default")
      (node (ref "U6") (pin "7") (pinfunction "I.C._7") (pintype "power_in"))
    )
    (net (code "72") (name "unconnected-(U7-FAULT_N-Pad1)") (class "Default")
      (node (ref "U7") (pin "1") (pinfunction "FAULT_N_1") (pintype "open_collector"))
    )
    (net (code "73") (name "unconnected-(U8-PA0-Pad5)") (class "Default")
      (node (ref "U8") (pin "5") (pinfunction "PA0_5") (pintype "bidirectional"))
    )
    (net (code "74") (name "unconnected-(U8-PF0-OSC-IN-Pad2)") (class "Default")
      (node (ref "U8") (pin "2") (pinfunction "PF0-OSC-IN_2") (pintype "bidirectional"))
    )
    (net (code "75") (name "unconnected-(U8-PF0-OSC-OUT-Pad3)") (class "Default")
      (node (ref "U8") (pin "3") (pinfunction "PF0-OSC-OUT_3") (pintype "bidirectional"))
    )
    (net (code "76") (name "unconnected-(U8-VSS-Pad16)") (class "Default")
      (node (ref "U8") (pin "16") (pinfunction "VSS_16") (pintype "power_in"))
    )
    (net (code "77") (name "unconnected-(U8-VSS-Pad32)") (class "Default")
      (node (ref "U8") (pin "32") (pinfunction "VSS_32") (pintype "power_in"))
    )
    (net (code "78") (name "unconnected-(U8-VSSA-Pad14)") (class "Default")
      (node (ref "U8") (pin "14") (pinfunction "VSSA_14") (pintype "power_in"))
    )
  )
)
